# Output.net
KiCad netlist of a schematic drawn in Altium Designer
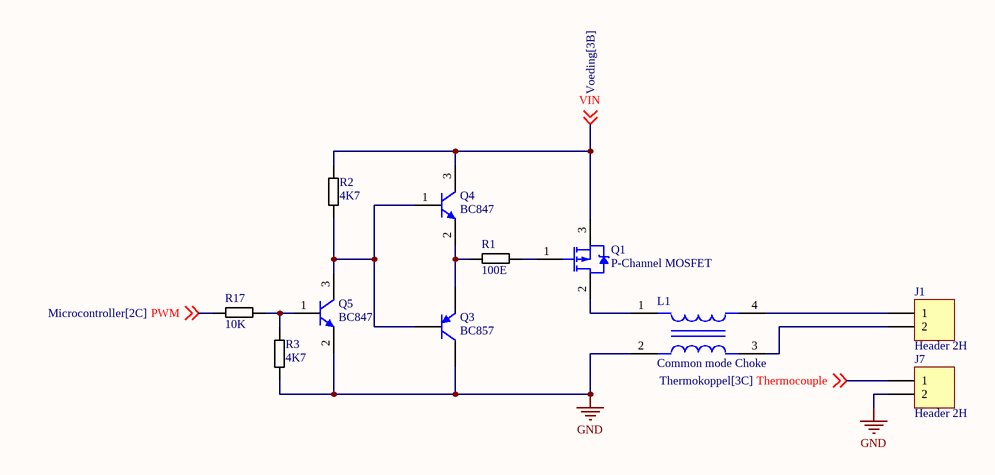
[diagram p0: Output.SchDoc]

(export (version "E")
  (design (tool "Eeschema 10.0.6"))
  (components
    (comp (ref "J1")
      (value "Header 2H")
      (footprint "Connector_2x1_p_5mm")
      (description "Header, 2-Pin, Right Angle")
      (fields (field (name "PUBLISHER") "Altium Limited"))
      (libsource (lib "Miscellaneous Connectors") (part "Header 2H"))
    )
    (comp (ref "J7")
      (value "Header 2H")
      (footprint "Connector_2x1_p_5mm")
      (description "Header, 2-Pin, Right Angle")
      (fields (field (name "PUBLISHER") "Altium Limited"))
      (libsource (lib "Miscellaneous Connectors") (part "Header 2H"))
    )
    (comp (ref "L1")
      (value "Common mode Choke")
      (footprint "2545")
      (libsource (lib "Soldeerstation") (part "Common mode Choke"))
    )
    (comp (ref "Q1")
      (value "P-Channel MOSFET")
      (footprint "INF-PG-TO252-3-313_N")
      (fields (field (name "PARTNUMBER") "NTB5605PT4G") (field (name "MANUFACTURER") "On Semiconductor"))
      (libsource (lib "Soldeerstation") (part "P-Channel MOSFET"))
    )
    (comp (ref "Q3")
      (value "BC857")
      (footprint "FAIR-SOT23-3_V")
      (fields (field (name "MANUFACTURER") "On Semiconductor") (field (name "PARTNUMBER") "BC557BRL1G"))
      (libsource (lib "Soldeerstation") (part "PNP transistor"))
    )
    (comp (ref "Q4")
      (value "BC847")
      (footprint "FAIR-SOT23-3_V")
      (fields (field (name "MANUFACTURER") "On Semiconductor") (field (name "PARTNUMBER") "BC547BRL1G"))
      (libsource (lib "Soldeerstation") (part "NPN Transistor"))
    )
    (comp (ref "Q5")
      (value "BC847")
      (footprint "FAIR-SOT23-3_V")
      (fields (field (name "MANUFACTURER") "On Semiconductor") (field (name "PARTNUMBER") "BC547BRL1G"))
      (libsource (lib "Soldeerstation") (part "NPN Transistor"))
    )
    (comp (ref "R1")
      (value "100E")
      (footprint "RESC2013X50X30ML20T20")
      (fields (field (name "MANUFACTURER") "Vishay Dale") (field (name "PART NUMBER") "CRCW08050000Z0EA"))
      (libsource (lib "Soldeerstation") (part "Resistor"))
    )
    (comp (ref "R2")
      (value "4K7")
      (footprint "RESC2013X50X30ML20T20")
      (fields (field (name "MANUFACTURER") "Vishay Dale") (field (name "PART NUMBER") "CRCW08050000Z0EA"))
      (libsource (lib "Soldeerstation") (part "Resistor"))
    )
    (comp (ref "R3")
      (value "4K7")
      (footprint "RESC2013X50X30ML20T20")
      (fields (field (name "MANUFACTURER") "Vishay Dale") (field (name "PART NUMBER") "CRCW08050000Z0EA"))
      (libsource (lib "Soldeerstation") (part "Resistor"))
    )
    (comp (ref "R17")
      (value "10K")
      (footprint "RESC2013X50X30ML20T20")
      (fields (field (name "MANUFACTURER") "Vishay Dale") (field (name "PART NUMBER") "CRCW08050000Z0EA"))
      (libsource (lib "Soldeerstation") (part "Resistor"))
    )
  )
  (nets
    (net (code "1") (name "GND") (class "Default")
      (node (ref "J7") (pin "2") (pinfunction "2_2") (pintype "passive"))
      (node (ref "L1") (pin "2") (pinfunction "2_2") (pintype "passive"))
      (node (ref "Q3") (pin "3") (pinfunction "C_3") (pintype "passive"))
      (node (ref "Q5") (pin "2") (pinfunction "E_2") (pintype "passive"))
      (node (ref "R3") (pin "1") (pinfunction "1_1") (pintype "passive"))
    )
    (net (code "2") (name "Net-(J1-Pad1)") (class "Default")
      (node (ref "J1") (pin "1") (pinfunction "1_1") (pintype "passive"))
      (node (ref "L1") (pin "4") (pinfunction "4_4") (pintype "passive"))
    )
    (net (code "3") (name "Net-(J1-Pad2)") (class "Default")
      (node (ref "J1") (pin "2") (pinfunction "2_2") (pintype "passive"))
      (node (ref "L1") (pin "3") (pinfunction "3_3") (pintype "passive"))
    )
    (net (code "4") (name "Net-(Q1-D)") (class "Default")
      (node (ref "L1") (pin "1") (pinfunction "1_1") (pintype "passive"))
      (node (ref "Q1") (pin "2") (pinfunction "D_2") (pintype "passive"))
    )
    (net (code "5") (name "Net-(Q1-G)") (class "Default")
      (node (ref "Q1") (pin "1") (pinfunction "G_1") (pintype "passive"))
      (node (ref "R1") (pin "2") (pinfunction "2_2") (pintype "passive"))
    )
    (net (code "6") (name "Net-(Q3-B)") (class "Default")
      (node (ref "Q3") (pin "1") (pinfunction "B_1") (pintype "passive"))
      (node (ref "Q4") (pin "1") (pinfunction "B_1") (pintype "passive"))
      (node (ref "Q5") (pin "3") (pinfunction "C_3") (pintype "passive"))
      (node (ref "R2") (pin "1") (pinfunction "1_1") (pintype "passive"))
    )
    (net (code "7") (name "Net-(Q3-E)") (class "Default")
      (node (ref "Q3") (pin "2") (pinfunction "E_2") (pintype "passive"))
      (node (ref "Q4") (pin "2") (pinfunction "E_2") (pintype "passive"))
      (node (ref "R1") (pin "1") (pinfunction "1_1") (pintype "passive"))
    )
    (net (code "8") (name "Net-(Q5-B)") (class "Default")
      (node (ref "Q5") (pin "1") (pinfunction "B_1") (pintype "passive"))
      (node (ref "R17") (pin "2") (pinfunction "2_2") (pintype "passive"))
      (node (ref "R3") (pin "2") (pinfunction "2_2") (pintype "passive"))
    )
    (net (code "9") (name "PWM") (class "Default")
      (node (ref "R17") (pin "1") (pinfunction "1_1") (pintype "passive"))
    )
    (net (code "10") (name "Thermocouple") (class "Default")
      (node (ref "J7") (pin "1") (pinfunction "1_1") (pintype "passive"))
    )
    (net (code "11") (name "VIN") (class "Default")
      (node (ref "Q1") (pin "3") (pinfunction "S_3") (pintype "passive"))
      (node (ref "Q4") (pin "3") (pinfunction "C_3") (pintype "passive"))
      (node (ref "R2") (pin "2") (pinfunction "2_2") (pintype "passive"))
    )
  )
)
